# sch_CPU.net
KiCad netlist of a schematic drawn in Altium Designer
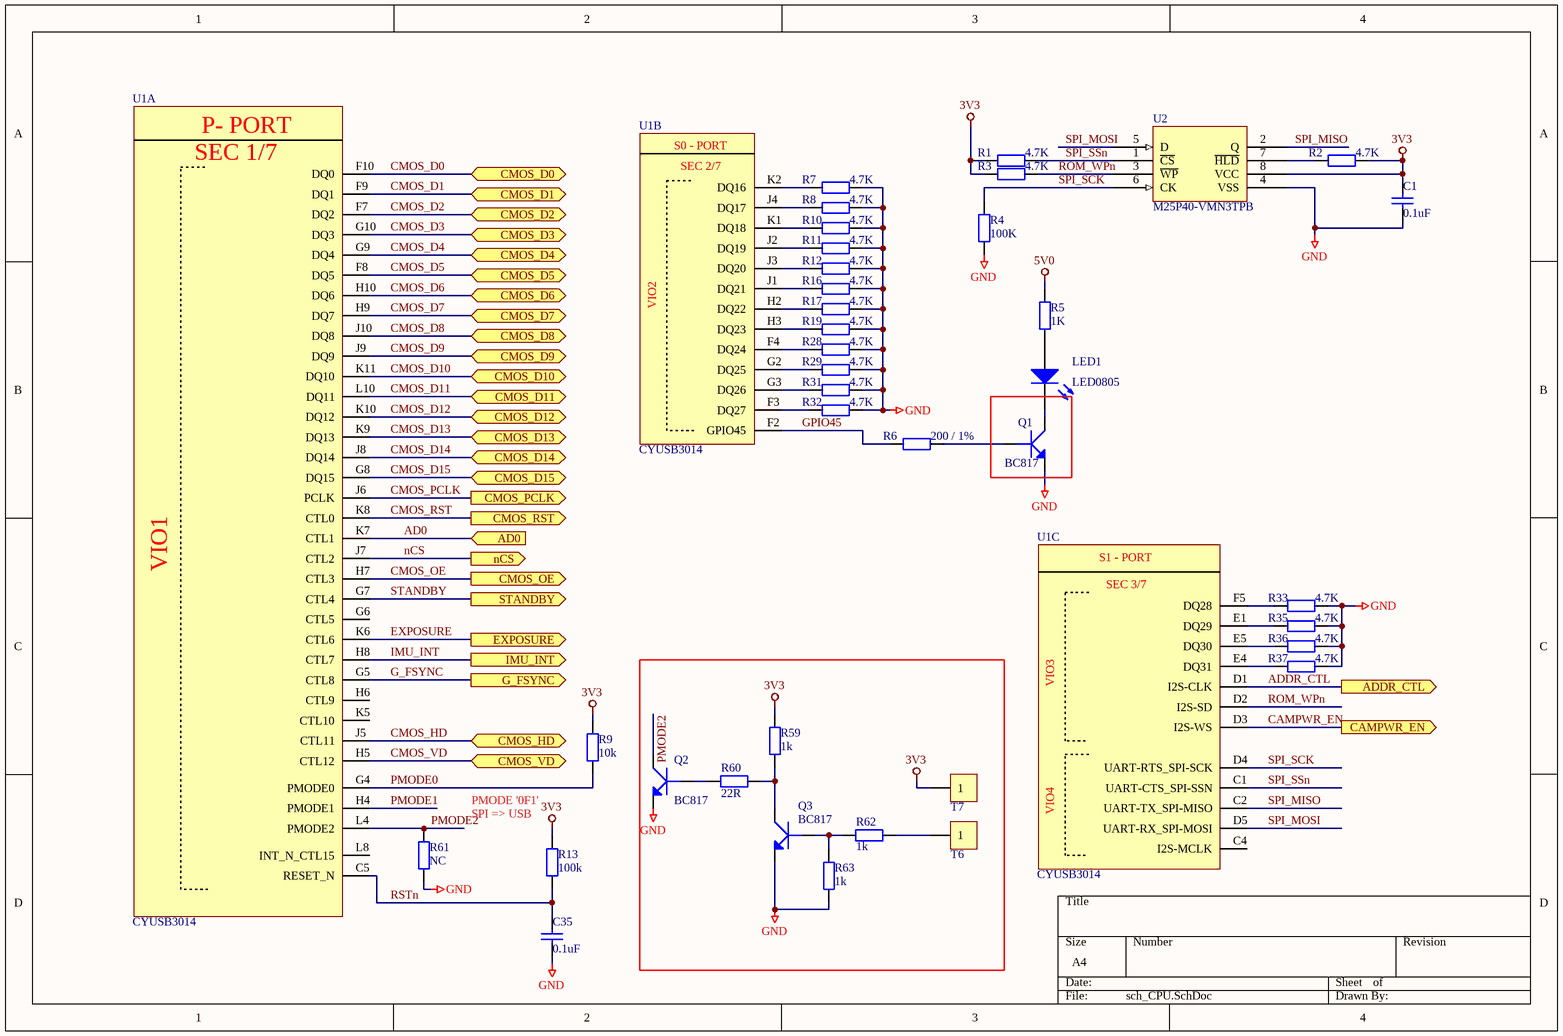
[diagram p0: sch_CPU.SchDoc]

(export (version "E")
  (design (tool "Eeschema 10.0.6"))
  (components
    (comp (ref "C1")
      (value "0.1uF")
      (footprint "0402C")
      (description "Capacitor")
      (fields (field (name "PUBLISHER") "Altium Limited"))
      (libsource (lib "Miscellaneous Devices") (part "Cap"))
    )
    (comp (ref "C35")
      (value "0.1uF")
      (footprint "0402C")
      (description "Capacitor")
      (fields (field (name "PUBLISHER") "Altium Limited"))
      (libsource (lib "Miscellaneous Devices") (part "Cap"))
    )
    (comp (ref "LED1")
      (value "LED0805")
      (footprint "LED0805A_L210W100H60")
      (description "发光二级管")
      (libsource (lib "TXW") (part "LED"))
    )
    (comp (ref "Q1")
      (value "BC817")
      (footprint "SOT-23L")
      (description "NPN Transistor")
      (libsource (lib "*") (part "NPN"))
    )
    (comp (ref "Q2")
      (value "BC817")
      (footprint "SOT-23L")
      (description "NPN Transistor")
      (libsource (lib "*") (part "NPN"))
    )
    (comp (ref "Q3")
      (value "BC817")
      (footprint "SOT-23L")
      (description "NPN Transistor")
      (libsource (lib "*") (part "NPN"))
    )
    (comp (ref "R1")
      (value "4.7K")
      (footprint "0402R")
      (description "Resistor")
      (fields (field (name "PUBLISHER") "Altium Limited"))
      (libsource (lib "") (part "Resistor_1"))
    )
    (comp (ref "R2")
      (value "4.7K")
      (footprint "0402R")
      (description "Resistor")
      (fields (field (name "PUBLISHER") "Altium Limited"))
      (libsource (lib "") (part "Resistor_1"))
    )
    (comp (ref "R3")
      (value "4.7K")
      (footprint "0402R")
      (description "Resistor")
      (fields (field (name "PUBLISHER") "Altium Limited"))
      (libsource (lib "") (part "Resistor_1"))
    )
    (comp (ref "R4")
      (value "100K")
      (footprint "0402R")
      (description "Resistor")
      (fields (field (name "PUBLISHER") "Altium Limited"))
      (libsource (lib "") (part "Resistor_2"))
    )
    (comp (ref "R5")
      (value "1K")
      (footprint "0402R")
      (description "Resistor")
      (fields (field (name "PUBLISHER") "Altium Limited"))
      (libsource (lib "SZG") (part "Resistor"))
    )
    (comp (ref "R6")
      (value "200 / 1%")
      (footprint "0402R")
      (description "Resistor")
      (fields (field (name "Comment") "200R") (field (name "PUBLISHER") "Altium Limited"))
      (libsource (lib "") (part "Resistor_1"))
    )
    (comp (ref "R7")
      (value "4.7K")
      (footprint "0402R")
      (description "Resistor")
      (fields (field (name "PUBLISHER") "Altium Limited"))
      (libsource (lib "") (part "Resistor_1"))
    )
    (comp (ref "R8")
      (value "4.7K")
      (footprint "0402R")
      (description "Resistor")
      (fields (field (name "PUBLISHER") "Altium Limited"))
      (libsource (lib "") (part "Resistor_1"))
    )
    (comp (ref "R9")
      (value "10k")
      (footprint "0402R")
      (description "Resistor")
      (fields (field (name "Comment") "10K") (field (name "PUBLISHER") "Altium Limited"))
      (libsource (lib "SZG") (part "Resistor"))
    )
    (comp (ref "R10")
      (value "4.7K")
      (footprint "0402R")
      (description "Resistor")
      (fields (field (name "PUBLISHER") "Altium Limited"))
      (libsource (lib "") (part "Resistor_1"))
    )
    (comp (ref "R11")
      (value "4.7K")
      (footprint "0402R")
      (description "Resistor")
      (fields (field (name "PUBLISHER") "Altium Limited"))
      (libsource (lib "") (part "Resistor_1"))
    )
    (comp (ref "R12")
      (value "4.7K")
      (footprint "0402R")
      (description "Resistor")
      (fields (field (name "PUBLISHER") "Altium Limited"))
      (libsource (lib "") (part "Resistor_1"))
    )
    (comp (ref "R13")
      (value "100k")
      (footprint "0402R")
      (description "Resistor")
      (fields (field (name "Comment") "100K") (field (name "PUBLISHER") "Altium Limited"))
      (libsource (lib "SZG") (part "Resistor"))
    )
    (comp (ref "R16")
      (value "4.7K")
      (footprint "0402R")
      (description "Resistor")
      (fields (field (name "PUBLISHER") "Altium Limited"))
      (libsource (lib "") (part "Resistor_1"))
    )
    (comp (ref "R17")
      (value "4.7K")
      (footprint "0402R")
      (description "Resistor")
      (fields (field (name "PUBLISHER") "Altium Limited"))
      (libsource (lib "") (part "Resistor_1"))
    )
    (comp (ref "R19")
      (value "4.7K")
      (footprint "0402R")
      (description "Resistor")
      (fields (field (name "PUBLISHER") "Altium Limited"))
      (libsource (lib "") (part "Resistor_1"))
    )
    (comp (ref "R28")
      (value "4.7K")
      (footprint "0402R")
      (description "Resistor")
      (fields (field (name "PUBLISHER") "Altium Limited"))
      (libsource (lib "") (part "Resistor_1"))
    )
    (comp (ref "R29")
      (value "4.7K")
      (footprint "0402R")
      (description "Resistor")
      (fields (field (name "PUBLISHER") "Altium Limited"))
      (libsource (lib "") (part "Resistor_1"))
    )
    (comp (ref "R31")
      (value "4.7K")
      (footprint "0402R")
      (description "Resistor")
      (fields (field (name "PUBLISHER") "Altium Limited"))
      (libsource (lib "") (part "Resistor_1"))
    )
    (comp (ref "R32")
      (value "4.7K")
      (footprint "0402R")
      (description "Resistor")
      (fields (field (name "PUBLISHER") "Altium Limited"))
      (libsource (lib "") (part "Resistor_1"))
    )
    (comp (ref "R33")
      (value "4.7K")
      (footprint "0402R")
      (description "Resistor")
      (fields (field (name "PUBLISHER") "Altium Limited"))
      (libsource (lib "") (part "Resistor_1"))
    )
    (comp (ref "R35")
      (value "4.7K")
      (footprint "0402R")
      (description "Resistor")
      (fields (field (name "PUBLISHER") "Altium Limited"))
      (libsource (lib "") (part "Resistor_1"))
    )
    (comp (ref "R36")
      (value "4.7K")
      (footprint "0402R")
      (description "Resistor")
      (fields (field (name "PUBLISHER") "Altium Limited"))
      (libsource (lib "") (part "Resistor_1"))
    )
    (comp (ref "R37")
      (value "4.7K")
      (footprint "0402R")
      (description "Resistor")
      (fields (field (name "PUBLISHER") "Altium Limited"))
      (libsource (lib "") (part "Resistor_1"))
    )
    (comp (ref "R59")
      (value "1k")
      (footprint "0402R")
      (description "Resistor")
      (fields (field (name "Comment") "1K") (field (name "PUBLISHER") "Altium Limited"))
      (libsource (lib "") (part "Resistor_2"))
    )
    (comp (ref "R60")
      (value "22R")
      (footprint "0402R")
      (description "Resistor")
      (fields (field (name "PUBLISHER") "Altium Limited"))
      (libsource (lib "") (part "Resistor_1"))
    )
    (comp (ref "R61")
      (value "NC")
      (footprint "0805R")
      (description "Resistor")
      (fields (field (name "PUBLISHER") "Altium Limited"))
      (libsource (lib "") (part "Resistor_2"))
    )
    (comp (ref "R62")
      (value "1k")
      (footprint "0402R")
      (description "Resistor")
      (fields (field (name "PUBLISHER") "Altium Limited"))
      (libsource (lib "") (part "Resistor_3"))
    )
    (comp (ref "R63")
      (value "1k")
      (footprint "0402R")
      (description "Resistor")
      (fields (field (name "PUBLISHER") "Altium Limited"))
      (libsource (lib "SZG") (part "Resistor"))
    )
    (comp (ref "T6")
      (value "CON1")
      (footprint "PAD_TP_D1.2")
      (description "Connector")
      (libsource (lib "SuperSchLib") (part "CON1"))
    )
    (comp (ref "T7")
      (value "CON1")
      (footprint "PAD_TP_D1.2")
      (description "Connector")
      (libsource (lib "SuperSchLib") (part "CON1"))
    )
    (comp (ref "U1")
      (value "CYUSB3014")
      (footprint "FBGA121_P80L100W100H11")
      (libsource (lib "TXW") (part "CYUSB3014"))
    )
    (comp (ref "U2")
      (value "M25P40-VMN3TPB")
      (footprint "SO8N_P127L50W40W62H17")
      (libsource (lib "TXW") (part "M25P40-VMN3TPB"))
    )
  )
  (nets
    (net (code "1") (name "/AD0") (class "Default")
      (node (ref "U1") (pin "K7") (pinfunction "CTL1_K7") (pintype "passive"))
    )
    (net (code "2") (name "/ADDR_CTL") (class "Default")
      (node (ref "U1") (pin "D1") (pinfunction "I2S-CLK_D1") (pintype "passive"))
    )
    (net (code "3") (name "/CAMPWR_EN") (class "Default")
      (node (ref "U1") (pin "D3") (pinfunction "I2S-WS_D3") (pintype "passive"))
    )
    (net (code "4") (name "/CMOS_D0") (class "Default")
      (node (ref "U1") (pin "F10") (pinfunction "DQ0_F10") (pintype "passive"))
    )
    (net (code "5") (name "/CMOS_D1") (class "Default")
      (node (ref "U1") (pin "F9") (pinfunction "DQ1_F9") (pintype "passive"))
    )
    (net (code "6") (name "/CMOS_D2") (class "Default")
      (node (ref "U1") (pin "F7") (pinfunction "DQ2_F7") (pintype "passive"))
    )
    (net (code "7") (name "/CMOS_D3") (class "Default")
      (node (ref "U1") (pin "G10") (pinfunction "DQ3_G10") (pintype "passive"))
    )
    (net (code "8") (name "/CMOS_D4") (class "Default")
      (node (ref "U1") (pin "G9") (pinfunction "DQ4_G9") (pintype "passive"))
    )
    (net (code "9") (name "/CMOS_D5") (class "Default")
      (node (ref "U1") (pin "F8") (pinfunction "DQ5_F8") (pintype "passive"))
    )
    (net (code "10") (name "/CMOS_D6") (class "Default")
      (node (ref "U1") (pin "H10") (pinfunction "DQ6_H10") (pintype "passive"))
    )
    (net (code "11") (name "/CMOS_D7") (class "Default")
      (node (ref "U1") (pin "H9") (pinfunction "DQ7_H9") (pintype "passive"))
    )
    (net (code "12") (name "/CMOS_D8") (class "Default")
      (node (ref "U1") (pin "J10") (pinfunction "DQ8_J10") (pintype "passive"))
    )
    (net (code "13") (name "/CMOS_D9") (class "Default")
      (node (ref "U1") (pin "J9") (pinfunction "DQ9_J9") (pintype "passive"))
    )
    (net (code "14") (name "/CMOS_D10") (class "Default")
      (node (ref "U1") (pin "K11") (pinfunction "DQ10_K11") (pintype "passive"))
    )
    (net (code "15") (name "/CMOS_D11") (class "Default")
      (node (ref "U1") (pin "L10") (pinfunction "DQ11_L10") (pintype "passive"))
    )
    (net (code "16") (name "/CMOS_D12") (class "Default")
      (node (ref "U1") (pin "K10") (pinfunction "DQ12_K10") (pintype "passive"))
    )
    (net (code "17") (name "/CMOS_D13") (class "Default")
      (node (ref "U1") (pin "K9") (pinfunction "DQ13_K9") (pintype "passive"))
    )
    (net (code "18") (name "/CMOS_D14") (class "Default")
      (node (ref "U1") (pin "J8") (pinfunction "DQ14_J8") (pintype "passive"))
    )
    (net (code "19") (name "/CMOS_D15") (class "Default")
      (node (ref "U1") (pin "G8") (pinfunction "DQ15_G8") (pintype "passive"))
    )
    (net (code "20") (name "/CMOS_HD") (class "Default")
      (node (ref "U1") (pin "J5") (pinfunction "CTL11_J5") (pintype "passive"))
    )
    (net (code "21") (name "/CMOS_OE") (class "Default")
      (node (ref "U1") (pin "H7") (pinfunction "CTL3_H7") (pintype "passive"))
    )
    (net (code "22") (name "/CMOS_PCLK") (class "Default")
      (node (ref "U1") (pin "J6") (pinfunction "PCLK_J6") (pintype "passive"))
    )
    (net (code "23") (name "/CMOS_RST") (class "Default")
      (node (ref "U1") (pin "K8") (pinfunction "CTL0_K8") (pintype "passive"))
    )
    (net (code "24") (name "/CMOS_VD") (class "Default")
      (node (ref "U1") (pin "H5") (pinfunction "CTL12_H5") (pintype "passive"))
    )
    (net (code "25") (name "/EXPOSURE") (class "Default")
      (node (ref "U1") (pin "K6") (pinfunction "CTL6_K6") (pintype "passive"))
    )
    (net (code "26") (name "/GPIO45") (class "Default")
      (node (ref "R6") (pin "1") (pinfunction "1_1") (pintype "passive"))
      (node (ref "U1") (pin "F2") (pinfunction "GPIO45_F2") (pintype "passive"))
    )
    (net (code "27") (name "/G_FSYNC") (class "Default")
      (node (ref "U1") (pin "G5") (pinfunction "CTL8_G5") (pintype "passive"))
    )
    (net (code "28") (name "/IMU_INT") (class "Default")
      (node (ref "U1") (pin "H8") (pinfunction "CTL7_H8") (pintype "passive"))
    )
    (net (code "29") (name "/PMODE0") (class "Default")
      (node (ref "R9") (pin "2") (pinfunction "2_2") (pintype "passive"))
      (node (ref "U1") (pin "G4") (pinfunction "PMODE0_G4") (pintype "passive"))
    )
    (net (code "30") (name "/PMODE1") (class "Default")
      (node (ref "U1") (pin "H4") (pinfunction "PMODE1_H4") (pintype "passive"))
    )
    (net (code "31") (name "/PMODE2") (class "Default")
      (node (ref "Q2") (pin "3") (pinfunction "C_3") (pintype "passive"))
      (node (ref "R61") (pin "2") (pinfunction "2_2") (pintype "passive"))
      (node (ref "U1") (pin "L4") (pinfunction "PMODE2_L4") (pintype "passive"))
    )
    (net (code "32") (name "/ROM_WPn") (class "Default")
      (node (ref "R3") (pin "2") (pinfunction "2_2") (pintype "passive"))
      (node (ref "U1") (pin "D2") (pinfunction "I2S-SD_D2") (pintype "passive"))
      (node (ref "U2") (pin "3") (pinfunction "~{WP}_3") (pintype "passive"))
    )
    (net (code "33") (name "/RSTn") (class "Default")
      (node (ref "C35") (pin "2") (pinfunction "2_2") (pintype "passive"))
      (node (ref "R13") (pin "2") (pinfunction "2_2") (pintype "passive"))
      (node (ref "U1") (pin "C5") (pinfunction "RESET_N_C5") (pintype "passive"))
    )
    (net (code "34") (name "/SPI_MISO") (class "Default")
      (node (ref "U1") (pin "C2") (pinfunction "UART-TX_SPI-MISO_C2") (pintype "passive"))
      (node (ref "U2") (pin "2") (pinfunction "Q_2") (pintype "passive"))
    )
    (net (code "35") (name "/SPI_MOSI") (class "Default")
      (node (ref "U1") (pin "D5") (pinfunction "UART-RX_SPI-MOSI_D5") (pintype "passive"))
      (node (ref "U2") (pin "5") (pinfunction "D_5") (pintype "input"))
    )
    (net (code "36") (name "/SPI_SCK") (class "Default")
      (node (ref "R4") (pin "2") (pinfunction "2_2") (pintype "passive"))
      (node (ref "U1") (pin "D4") (pinfunction "UART-RTS_SPI-SCK_D4") (pintype "passive"))
      (node (ref "U2") (pin "6") (pinfunction "CK_6") (pintype "input"))
    )
    (net (code "37") (name "/SPI_SSn") (class "Default")
      (node (ref "R1") (pin "2") (pinfunction "2_2") (pintype "passive"))
      (node (ref "U1") (pin "C1") (pinfunction "UART-CTS_SPI-SSN_C1") (pintype "passive"))
      (node (ref "U2") (pin "1") (pinfunction "~{CS}_1") (pintype "passive"))
    )
    (net (code "38") (name "/STANDBY") (class "Default")
      (node (ref "U1") (pin "G7") (pinfunction "CTL4_G7") (pintype "passive"))
    )
    (net (code "39") (name "/nCS") (class "Default")
      (node (ref "U1") (pin "J7") (pinfunction "CTL2_J7") (pintype "passive"))
    )
    (net (code "40") (name "3V3") (class "Default")
      (node (ref "C1") (pin "2") (pinfunction "2_2") (pintype "passive"))
      (node (ref "R1") (pin "1") (pinfunction "1_1") (pintype "passive"))
      (node (ref "R13") (pin "1") (pinfunction "1_1") (pintype "passive"))
      (node (ref "R2") (pin "2") (pinfunction "2_2") (pintype "passive"))
      (node (ref "R3") (pin "1") (pinfunction "1_1") (pintype "passive"))
      (node (ref "R59") (pin "2") (pinfunction "2_2") (pintype "passive"))
      (node (ref "R9") (pin "1") (pinfunction "1_1") (pintype "passive"))
      (node (ref "T7") (pin "1") (pinfunction "1_1") (pintype "passive"))
      (node (ref "U2") (pin "8") (pinfunction "VCC_8") (pintype "passive"))
    )
    (net (code "41") (name "5V0") (class "Default")
      (node (ref "R5") (pin "1") (pinfunction "1_1") (pintype "passive"))
    )
    (net (code "42") (name "GND") (class "Default")
      (node (ref "C1") (pin "1") (pinfunction "1_1") (pintype "passive"))
      (node (ref "C35") (pin "1") (pinfunction "1_1") (pintype "passive"))
      (node (ref "Q1") (pin "2") (pinfunction "E_2") (pintype "passive"))
      (node (ref "Q2") (pin "2") (pinfunction "E_2") (pintype "passive"))
      (node (ref "Q3") (pin "2") (pinfunction "E_2") (pintype "passive"))
      (node (ref "R10") (pin "2") (pinfunction "2_2") (pintype "passive"))
      (node (ref "R11") (pin "2") (pinfunction "2_2") (pintype "passive"))
      (node (ref "R12") (pin "2") (pinfunction "2_2") (pintype "passive"))
      (node (ref "R16") (pin "2") (pinfunction "2_2") (pintype "passive"))
      (node (ref "R17") (pin "2") (pinfunction "2_2") (pintype "passive"))
      (node (ref "R19") (pin "2") (pinfunction "2_2") (pintype "passive"))
      (node (ref "R28") (pin "2") (pinfunction "2_2") (pintype "passive"))
      (node (ref "R29") (pin "2") (pinfunction "2_2") (pintype "passive"))
      (node (ref "R31") (pin "2") (pinfunction "2_2") (pintype "passive"))
      (node (ref "R32") (pin "2") (pinfunction "2_2") (pintype "passive"))
      (node (ref "R33") (pin "2") (pinfunction "2_2") (pintype "passive"))
      (node (ref "R35") (pin "2") (pinfunction "2_2") (pintype "passive"))
      (node (ref "R36") (pin "2") (pinfunction "2_2") (pintype "passive"))
      (node (ref "R37") (pin "2") (pinfunction "2_2") (pintype "passive"))
      (node (ref "R4") (pin "1") (pinfunction "1_1") (pintype "passive"))
      (node (ref "R61") (pin "1") (pinfunction "1_1") (pintype "passive"))
      (node (ref "R63") (pin "2") (pinfunction "2_2") (pintype "passive"))
      (node (ref "R7") (pin "2") (pinfunction "2_2") (pintype "passive"))
      (node (ref "R8") (pin "2") (pinfunction "2_2") (pintype "passive"))
      (node (ref "U2") (pin "4") (pinfunction "VSS_4") (pintype "passive"))
    )
    (net (code "43") (name "Net-(LED1-A)") (class "Default")
      (node (ref "LED1") (pin "1") (pinfunction "A_1") (pintype "passive"))
      (node (ref "R5") (pin "2") (pinfunction "2_2") (pintype "passive"))
    )
    (net (code "44") (name "Net-(LED1-K)") (class "Default")
      (node (ref "LED1") (pin "2") (pinfunction "K_2") (pintype "passive"))
      (node (ref "Q1") (pin "3") (pinfunction "C_3") (pintype "passive"))
    )
    (net (code "45") (name "Net-(Q1-B)") (class "Default")
      (node (ref "Q1") (pin "1") (pinfunction "B_1") (pintype "passive"))
      (node (ref "R6") (pin "2") (pinfunction "2_2") (pintype "passive"))
    )
    (net (code "46") (name "Net-(Q2-B)") (class "Default")
      (node (ref "Q2") (pin "1") (pinfunction "B_1") (pintype "passive"))
      (node (ref "R60") (pin "1") (pinfunction "1_1") (pintype "passive"))
    )
    (net (code "47") (name "Net-(Q3-B)") (class "Default")
      (node (ref "Q3") (pin "1") (pinfunction "B_1") (pintype "passive"))
      (node (ref "R62") (pin "2") (pinfunction "2_2") (pintype "passive"))
      (node (ref "R63") (pin "1") (pinfunction "1_1") (pintype "passive"))
    )
    (net (code "48") (name "Net-(Q3-C)") (class "Default")
      (node (ref "Q3") (pin "3") (pinfunction "C_3") (pintype "passive"))
      (node (ref "R59") (pin "1") (pinfunction "1_1") (pintype "passive"))
      (node (ref "R60") (pin "2") (pinfunction "2_2") (pintype "passive"))
    )
    (net (code "49") (name "Net-(R62-Pad1)") (class "Default")
      (node (ref "R62") (pin "1") (pinfunction "1_1") (pintype "passive"))
      (node (ref "T6") (pin "1") (pinfunction "1_1") (pintype "passive"))
    )
    (net (code "50") (name "Net-(U1B-DQ16)") (class "Default")
      (node (ref "R7") (pin "1") (pinfunction "1_1") (pintype "passive"))
      (node (ref "U1") (pin "K2") (pinfunction "DQ16_K2") (pintype "passive"))
    )
    (net (code "51") (name "Net-(U1B-DQ17)") (class "Default")
      (node (ref "R8") (pin "1") (pinfunction "1_1") (pintype "passive"))
      (node (ref "U1") (pin "J4") (pinfunction "DQ17_J4") (pintype "passive"))
    )
    (net (code "52") (name "Net-(U1B-DQ18)") (class "Default")
      (node (ref "R10") (pin "1") (pinfunction "1_1") (pintype "passive"))
      (node (ref "U1") (pin "K1") (pinfunction "DQ18_K1") (pintype "passive"))
    )
    (net (code "53") (name "Net-(U1B-DQ19)") (class "Default")
      (node (ref "R11") (pin "1") (pinfunction "1_1") (pintype "passive"))
      (node (ref "U1") (pin "J2") (pinfunction "DQ19_J2") (pintype "passive"))
    )
    (net (code "54") (name "Net-(U1B-DQ20)") (class "Default")
      (node (ref "R12") (pin "1") (pinfunction "1_1") (pintype "passive"))
      (node (ref "U1") (pin "J3") (pinfunction "DQ20_J3") (pintype "passive"))
    )
    (net (code "55") (name "Net-(U1B-DQ21)") (class "Default")
      (node (ref "R16") (pin "1") (pinfunction "1_1") (pintype "passive"))
      (node (ref "U1") (pin "J1") (pinfunction "DQ21_J1") (pintype "passive"))
    )
    (net (code "56") (name "Net-(U1B-DQ22)") (class "Default")
      (node (ref "R17") (pin "1") (pinfunction "1_1") (pintype "passive"))
      (node (ref "U1") (pin "H2") (pinfunction "DQ22_H2") (pintype "passive"))
    )
    (net (code "57") (name "Net-(U1B-DQ23)") (class "Default")
      (node (ref "R19") (pin "1") (pinfunction "1_1") (pintype "passive"))
      (node (ref "U1") (pin "H3") (pinfunction "DQ23_H3") (pintype "passive"))
    )
    (net (code "58") (name "Net-(U1B-DQ24)") (class "Default")
      (node (ref "R28") (pin "1") (pinfunction "1_1") (pintype "passive"))
      (node (ref "U1") (pin "F4") (pinfunction "DQ24_F4") (pintype "passive"))
    )
    (net (code "59") (name "Net-(U1B-DQ25)") (class "Default")
      (node (ref "R29") (pin "1") (pinfunction "1_1") (pintype "passive"))
      (node (ref "U1") (pin "G2") (pinfunction "DQ25_G2") (pintype "passive"))
    )
    (net (code "60") (name "Net-(U1B-DQ26)") (class "Default")
      (node (ref "R31") (pin "1") (pinfunction "1_1") (pintype "passive"))
      (node (ref "U1") (pin "G3") (pinfunction "DQ26_G3") (pintype "passive"))
    )
    (net (code "61") (name "Net-(U1B-DQ27)") (class "Default")
      (node (ref "R32") (pin "1") (pinfunction "1_1") (pintype "passive"))
      (node (ref "U1") (pin "F3") (pinfunction "DQ27_F3") (pintype "passive"))
    )
    (net (code "62") (name "Net-(U1C-DQ28)") (class "Default")
      (node (ref "R33") (pin "1") (pinfunction "1_1") (pintype "passive"))
      (node (ref "U1") (pin "F5") (pinfunction "DQ28_F5") (pintype "passive"))
    )
    (net (code "63") (name "Net-(U1C-DQ29)") (class "Default")
      (node (ref "R35") (pin "1") (pinfunction "1_1") (pintype "passive"))
      (node (ref "U1") (pin "E1") (pinfunction "DQ29_E1") (pintype "passive"))
    )
    (net (code "64") (name "Net-(U1C-DQ30)") (class "Default")
      (node (ref "R36") (pin "1") (pinfunction "1_1") (pintype "passive"))
      (node (ref "U1") (pin "E5") (pinfunction "DQ30_E5") (pintype "passive"))
    )
    (net (code "65") (name "Net-(U1C-DQ31)") (class "Default")
      (node (ref "R37") (pin "1") (pinfunction "1_1") (pintype "passive"))
      (node (ref "U1") (pin "E4") (pinfunction "DQ31_E4") (pintype "passive"))
    )
    (net (code "66") (name "Net-(U2-~{HLD})") (class "Default")
      (node (ref "R2") (pin "1") (pinfunction "1_1") (pintype "passive"))
      (node (ref "U2") (pin "7") (pinfunction "~{HLD}_7") (pintype "passive"))
    )
    (net (code "67") (name "unconnected-(U1A-CTL5-PadG6)") (class "Default")
      (node (ref "U1") (pin "G6") (pinfunction "CTL5_G6") (pintype "passive"))
    )
    (net (code "68") (name "unconnected-(U1A-CTL9-PadH6)") (class "Default")
      (node (ref "U1") (pin "H6") (pinfunction "CTL9_H6") (pintype "passive"))
    )
    (net (code "69") (name "unconnected-(U1A-CTL10-PadK5)") (class "Default")
      (node (ref "U1") (pin "K5") (pinfunction "CTL10_K5") (pintype "passive"))
    )
    (net (code "70") (name "unconnected-(U1A-INT_N_CTL15-PadL8)") (class "Default")
      (node (ref "U1") (pin "L8") (pinfunction "INT_N_CTL15_L8") (pintype "passive"))
    )
    (net (code "71") (name "unconnected-(U1C-I2S-MCLK-PadC4)") (class "Default")
      (node (ref "U1") (pin "C4") (pinfunction "I2S-MCLK_C4") (pintype "passive"))
    )
  )
)
